# wuerfel.net
KiCad netlist of a schematic drawn in EAGLE
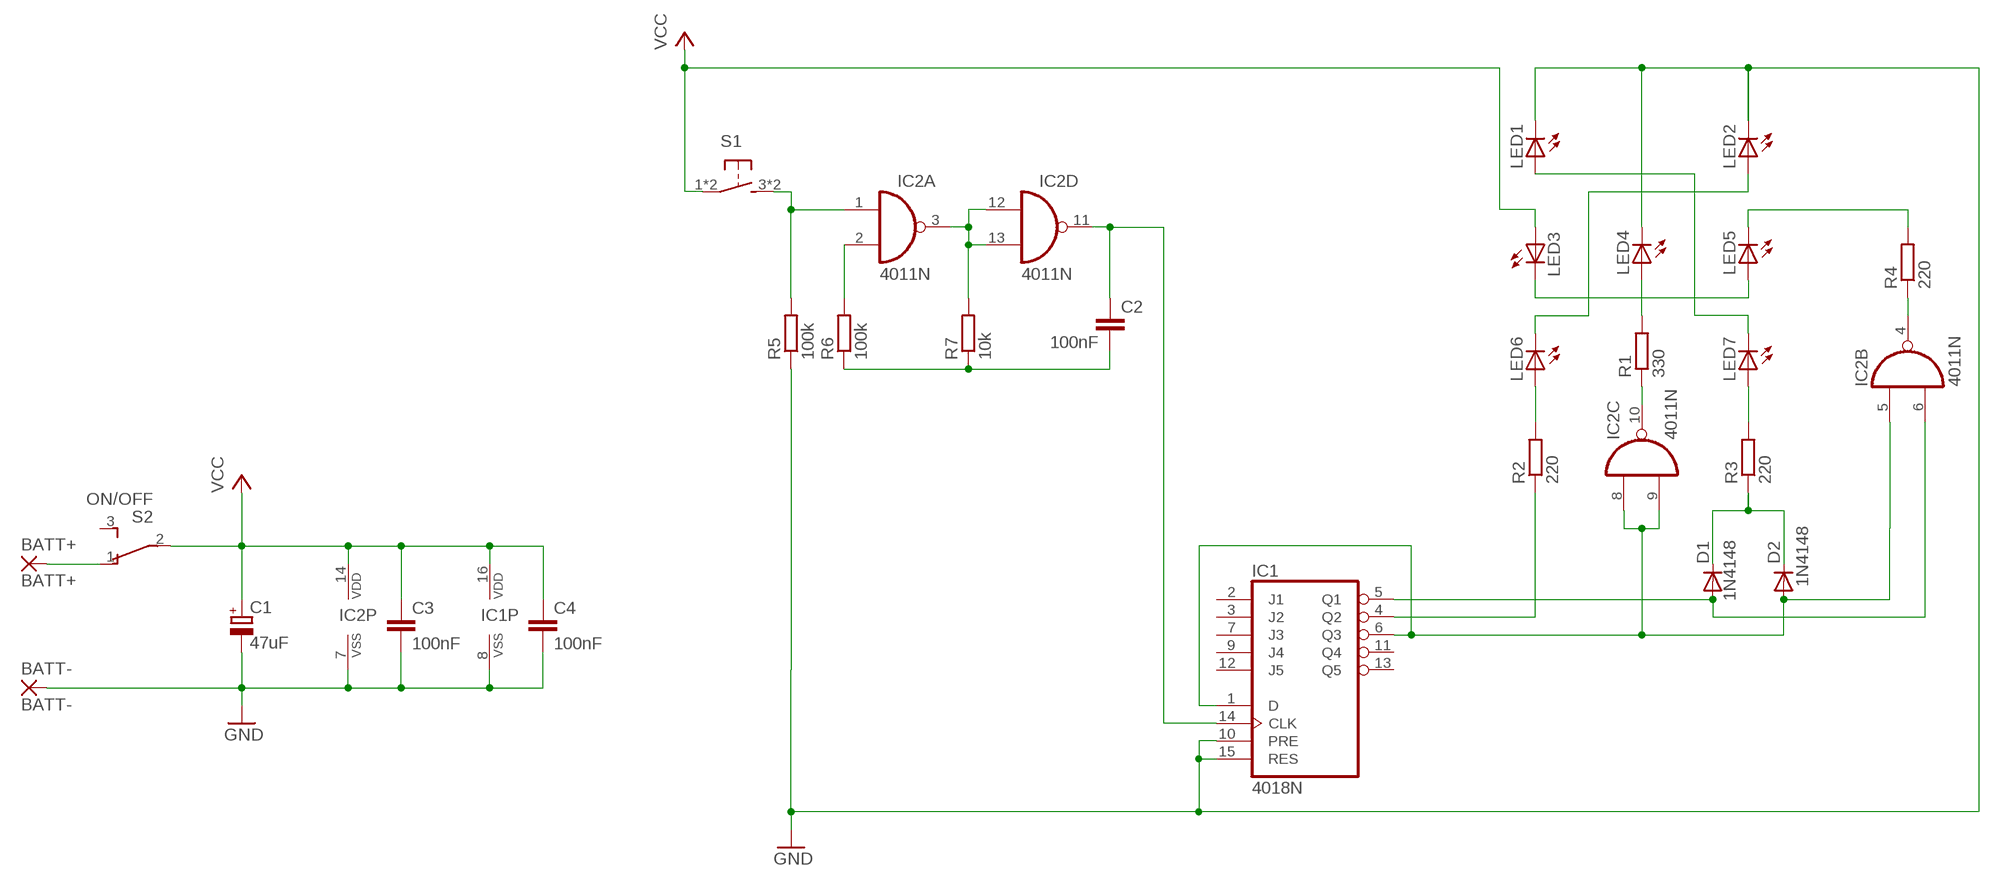
[diagram p0: schematic, sheet 1]

(export (version "E")
  (design (tool "Eeschema 10.0.6"))
  (components
    (comp (ref "BATT+")
      (value "BATT+")
      (footprint "eagle-import:2,54_0,8")
      (libsource (lib "eagle-import") (part "WIREPAD2,54/0,8"))
    )
    (comp (ref "BATT-")
      (value "BATT-")
      (footprint "eagle-import:2,54_0,8")
      (libsource (lib "eagle-import") (part "WIREPAD2,54/0,8"))
    )
    (comp (ref "C1")
      (value "47uF")
      (footprint "eagle-import:E2,5-5-L-12")
      (libsource (lib "eagle-import") (part "CPOL-EUE2.5-5-L-12"))
    )
    (comp (ref "C2")
      (value "100nF")
      (footprint "eagle-import:C025-025X050")
      (libsource (lib "eagle-import") (part "C-EU025-025X050"))
    )
    (comp (ref "C3")
      (value "100nF")
      (footprint "eagle-import:C025-025X050")
      (libsource (lib "eagle-import") (part "C-EU025-025X050"))
    )
    (comp (ref "C4")
      (value "100nF")
      (footprint "eagle-import:C025-025X050")
      (libsource (lib "eagle-import") (part "C-EU025-025X050"))
    )
    (comp (ref "D1")
      (value "1N4148")
      (footprint "eagle-import:DO35-10")
      (libsource (lib "eagle-import") (part "1N4148DO35-10"))
    )
    (comp (ref "D2")
      (value "1N4148")
      (footprint "eagle-import:DO35-10")
      (libsource (lib "eagle-import") (part "1N4148DO35-10"))
    )
    (comp (ref "IC1")
      (value "4018N")
      (footprint "eagle-import:DIL16")
      (libsource (lib "eagle-import") (part "4018N"))
    )
    (comp (ref "IC2")
      (value "4011N")
      (footprint "eagle-import:DIL14")
      (libsource (lib "eagle-import") (part "4011N"))
    )
    (comp (ref "LED1")
      (value "LED5MM")
      (footprint "eagle-import:LED5MM")
      (libsource (lib "eagle-import") (part "LED5MM"))
    )
    (comp (ref "LED2")
      (value "LED5MM")
      (footprint "eagle-import:LED5MM")
      (libsource (lib "eagle-import") (part "LED5MM"))
    )
    (comp (ref "LED3")
      (value "LED5MM")
      (footprint "eagle-import:LED5MM")
      (libsource (lib "eagle-import") (part "LED5MM"))
    )
    (comp (ref "LED4")
      (value "LED5MM")
      (footprint "eagle-import:LED5MM")
      (libsource (lib "eagle-import") (part "LED5MM"))
    )
    (comp (ref "LED5")
      (value "LED5MM")
      (footprint "eagle-import:LED5MM")
      (libsource (lib "eagle-import") (part "LED5MM"))
    )
    (comp (ref "LED6")
      (value "LED5MM")
      (footprint "eagle-import:LED5MM")
      (libsource (lib "eagle-import") (part "LED5MM"))
    )
    (comp (ref "LED7")
      (value "LED5MM")
      (footprint "eagle-import:LED5MM")
      (libsource (lib "eagle-import") (part "LED5MM"))
    )
    (comp (ref "R1")
      (value "330")
      (footprint "eagle-import:0207_10")
      (libsource (lib "eagle-import") (part "R-EU_0207/10"))
    )
    (comp (ref "R2")
      (value "220")
      (footprint "eagle-import:0207_10")
      (libsource (lib "eagle-import") (part "R-EU_0207/10"))
    )
    (comp (ref "R3")
      (value "220")
      (footprint "eagle-import:0207_10")
      (libsource (lib "eagle-import") (part "R-EU_0207/10"))
    )
    (comp (ref "R4")
      (value "220")
      (footprint "eagle-import:0207_10")
      (libsource (lib "eagle-import") (part "R-EU_0207/10"))
    )
    (comp (ref "R5")
      (value "100k")
      (footprint "eagle-import:0207_10")
      (libsource (lib "eagle-import") (part "R-EU_0207/10"))
    )
    (comp (ref "R6")
      (value "100k")
      (footprint "eagle-import:0207_10")
      (libsource (lib "eagle-import") (part "R-EU_0207/10"))
    )
    (comp (ref "R7")
      (value "10k")
      (footprint "eagle-import:0207_10")
      (libsource (lib "eagle-import") (part "R-EU_0207/10"))
    )
    (comp (ref "S1")
      (value "TASTER8MM")
      (footprint "eagle-import:TASTER6X6")
      (libsource (lib "eagle-import") (part "TASTER8MM"))
    )
    (comp (ref "S2")
      (value "ON/OFF")
      (footprint "eagle-import:T215LB")
      (libsource (lib "eagle-import") (part "T215T215LB"))
    )
  )
  (nets
    (net (code "1") (name "GND") (class "Default")
      (node (ref "BATT-") (pin "1") (pinfunction "P_1") (pintype "passive"))
      (node (ref "C1") (pin "-") (pinfunction "-_-") (pintype "passive"))
      (node (ref "C3") (pin "2") (pinfunction "2_2") (pintype "passive"))
      (node (ref "C4") (pin "2") (pinfunction "2_2") (pintype "passive"))
      (node (ref "IC1") (pin "10") (pinfunction "PRE_10") (pintype "input"))
      (node (ref "IC1") (pin "15") (pinfunction "RES_15") (pintype "input"))
      (node (ref "IC1") (pin "8") (pinfunction "VSS_8") (pintype "power_in"))
      (node (ref "IC2") (pin "7") (pinfunction "VSS_7") (pintype "power_in"))
      (node (ref "LED1") (pin "K") (pinfunction "C_K") (pintype "passive"))
      (node (ref "LED2") (pin "K") (pinfunction "C_K") (pintype "passive"))
      (node (ref "LED4") (pin "K") (pinfunction "C_K") (pintype "passive"))
      (node (ref "R5") (pin "1") (pinfunction "1_1") (pintype "passive"))
    )
    (net (code "2") (name "Net-(BATT+-P)") (class "Default")
      (node (ref "BATT+") (pin "1") (pinfunction "P_1") (pintype "passive"))
      (node (ref "S2") (pin "1") (pinfunction "O_1") (pintype "passive"))
    )
    (net (code "3") (name "Net-(C2-Pad2)") (class "Default")
      (node (ref "C2") (pin "2") (pinfunction "2_2") (pintype "passive"))
      (node (ref "R6") (pin "1") (pinfunction "1_1") (pintype "passive"))
      (node (ref "R7") (pin "1") (pinfunction "1_1") (pintype "passive"))
    )
    (net (code "4") (name "Net-(D1-PadC)") (class "Default")
      (node (ref "D1") (pin "C") (pinfunction "C_C") (pintype "passive"))
      (node (ref "D2") (pin "C") (pinfunction "C_C") (pintype "passive"))
      (node (ref "R3") (pin "1") (pinfunction "1_1") (pintype "passive"))
    )
    (net (code "5") (name "Net-(IC1A-CLK)") (class "Default")
      (node (ref "C2") (pin "1") (pinfunction "1_1") (pintype "passive"))
      (node (ref "IC1") (pin "14") (pinfunction "CLK_14") (pintype "input"))
      (node (ref "IC2") (pin "11") (pinfunction "O_11") (pintype "output"))
    )
    (net (code "6") (name "Net-(IC1A-D)") (class "Default")
      (node (ref "D2") (pin "A") (pinfunction "A_A") (pintype "passive"))
      (node (ref "IC1") (pin "1") (pinfunction "D_1") (pintype "input"))
      (node (ref "IC1") (pin "6") (pinfunction "Q3_6") (pintype "output"))
      (node (ref "IC2") (pin "5") (pinfunction "I0_5") (pintype "input"))
      (node (ref "IC2") (pin "8") (pinfunction "I0_8") (pintype "input"))
      (node (ref "IC2") (pin "9") (pinfunction "I1_9") (pintype "input"))
    )
    (net (code "7") (name "Net-(IC1A-Q1)") (class "Default")
      (node (ref "D1") (pin "A") (pinfunction "A_A") (pintype "passive"))
      (node (ref "IC1") (pin "5") (pinfunction "Q1_5") (pintype "output"))
      (node (ref "IC2") (pin "6") (pinfunction "I1_6") (pintype "input"))
    )
    (net (code "8") (name "Net-(IC1A-Q2)") (class "Default")
      (node (ref "IC1") (pin "4") (pinfunction "Q2_4") (pintype "output"))
      (node (ref "R2") (pin "1") (pinfunction "1_1") (pintype "passive"))
    )
    (net (code "9") (name "Net-(IC2A-I0)") (class "Default")
      (node (ref "IC2") (pin "1") (pinfunction "I0_1") (pintype "input"))
      (node (ref "R5") (pin "2") (pinfunction "2_2") (pintype "passive"))
      (node (ref "S1") (pin "3") (pinfunction "3_3") (pintype "passive"))
      (node (ref "S1") (pin "4") (pinfunction "3_4") (pintype "passive"))
    )
    (net (code "10") (name "Net-(IC2A-I1)") (class "Default")
      (node (ref "IC2") (pin "2") (pinfunction "I1_2") (pintype "input"))
      (node (ref "R6") (pin "2") (pinfunction "2_2") (pintype "passive"))
    )
    (net (code "11") (name "Net-(IC2A-O)") (class "Default")
      (node (ref "IC2") (pin "12") (pinfunction "I0_12") (pintype "input"))
      (node (ref "IC2") (pin "13") (pinfunction "I1_13") (pintype "input"))
      (node (ref "IC2") (pin "3") (pinfunction "O_3") (pintype "output"))
      (node (ref "R7") (pin "2") (pinfunction "2_2") (pintype "passive"))
    )
    (net (code "12") (name "Net-(IC2B-O)") (class "Default")
      (node (ref "IC2") (pin "4") (pinfunction "O_4") (pintype "output"))
      (node (ref "R4") (pin "1") (pinfunction "1_1") (pintype "passive"))
    )
    (net (code "13") (name "Net-(IC2C-O)") (class "Default")
      (node (ref "IC2") (pin "10") (pinfunction "O_10") (pintype "output"))
      (node (ref "R1") (pin "1") (pinfunction "1_1") (pintype "passive"))
    )
    (net (code "14") (name "Net-(LED3-C)") (class "Default")
      (node (ref "LED3") (pin "K") (pinfunction "C_K") (pintype "passive"))
      (node (ref "LED5") (pin "A") (pinfunction "A_A") (pintype "passive"))
    )
    (net (code "15") (name "Net-(LED4-PadA)") (class "Default")
      (node (ref "LED4") (pin "A") (pinfunction "A_A") (pintype "passive"))
      (node (ref "R1") (pin "2") (pinfunction "2_2") (pintype "passive"))
    )
    (net (code "16") (name "Net-(LED5-C)") (class "Default")
      (node (ref "LED5") (pin "K") (pinfunction "C_K") (pintype "passive"))
      (node (ref "R4") (pin "2") (pinfunction "2_2") (pintype "passive"))
    )
    (net (code "17") (name "Net-(LED6-C)") (class "Default")
      (node (ref "LED2") (pin "A") (pinfunction "A_A") (pintype "passive"))
      (node (ref "LED6") (pin "K") (pinfunction "C_K") (pintype "passive"))
    )
    (net (code "18") (name "Net-(LED6-PadA)") (class "Default")
      (node (ref "LED6") (pin "A") (pinfunction "A_A") (pintype "passive"))
      (node (ref "R2") (pin "2") (pinfunction "2_2") (pintype "passive"))
    )
    (net (code "19") (name "Net-(LED7-C)") (class "Default")
      (node (ref "LED1") (pin "A") (pinfunction "A_A") (pintype "passive"))
      (node (ref "LED7") (pin "K") (pinfunction "C_K") (pintype "passive"))
    )
    (net (code "20") (name "Net-(LED7-PadA)") (class "Default")
      (node (ref "LED7") (pin "A") (pinfunction "A_A") (pintype "passive"))
      (node (ref "R3") (pin "2") (pinfunction "2_2") (pintype "passive"))
    )
    (net (code "21") (name "VCC") (class "Default")
      (node (ref "C1") (pin "+") (pinfunction "+_+") (pintype "passive"))
      (node (ref "C3") (pin "1") (pinfunction "1_1") (pintype "passive"))
      (node (ref "C4") (pin "1") (pinfunction "1_1") (pintype "passive"))
      (node (ref "IC1") (pin "16") (pinfunction "VDD_16") (pintype "power_in"))
      (node (ref "IC2") (pin "14") (pinfunction "VDD_14") (pintype "power_in"))
      (node (ref "LED3") (pin "A") (pinfunction "A_A") (pintype "passive"))
      (node (ref "S1") (pin "1") (pinfunction "1_1") (pintype "passive"))
      (node (ref "S1") (pin "2") (pinfunction "1_2") (pintype "passive"))
      (node (ref "S2") (pin "2") (pinfunction "P_2") (pintype "passive"))
    )
    (net (code "22") (name "unconnected-(IC1A-J1-Pad2)") (class "Default")
      (node (ref "IC1") (pin "2") (pinfunction "J1_2") (pintype "input"))
    )
    (net (code "23") (name "unconnected-(IC1A-J2-Pad3)") (class "Default")
      (node (ref "IC1") (pin "3") (pinfunction "J2_3") (pintype "input"))
    )
    (net (code "24") (name "unconnected-(IC1A-J3-Pad7)") (class "Default")
      (node (ref "IC1") (pin "7") (pinfunction "J3_7") (pintype "input"))
    )
    (net (code "25") (name "unconnected-(IC1A-J4-Pad9)") (class "Default")
      (node (ref "IC1") (pin "9") (pinfunction "J4_9") (pintype "input"))
    )
    (net (code "26") (name "unconnected-(IC1A-J5-Pad12)") (class "Default")
      (node (ref "IC1") (pin "12") (pinfunction "J5_12") (pintype "input"))
    )
    (net (code "27") (name "unconnected-(IC1A-Q4-Pad11)") (class "Default")
      (node (ref "IC1") (pin "11") (pinfunction "Q4_11") (pintype "output"))
    )
    (net (code "28") (name "unconnected-(IC1A-Q5-Pad13)") (class "Default")
      (node (ref "IC1") (pin "13") (pinfunction "Q5_13") (pintype "output"))
    )
    (net (code "29") (name "unconnected-(S2-S-Pad3)") (class "Default")
      (node (ref "S2") (pin "3") (pinfunction "S_3") (pintype "passive"))
    )
  )
)
